# schematic.net
KiCad netlist of a schematic drawn in EasyEDA
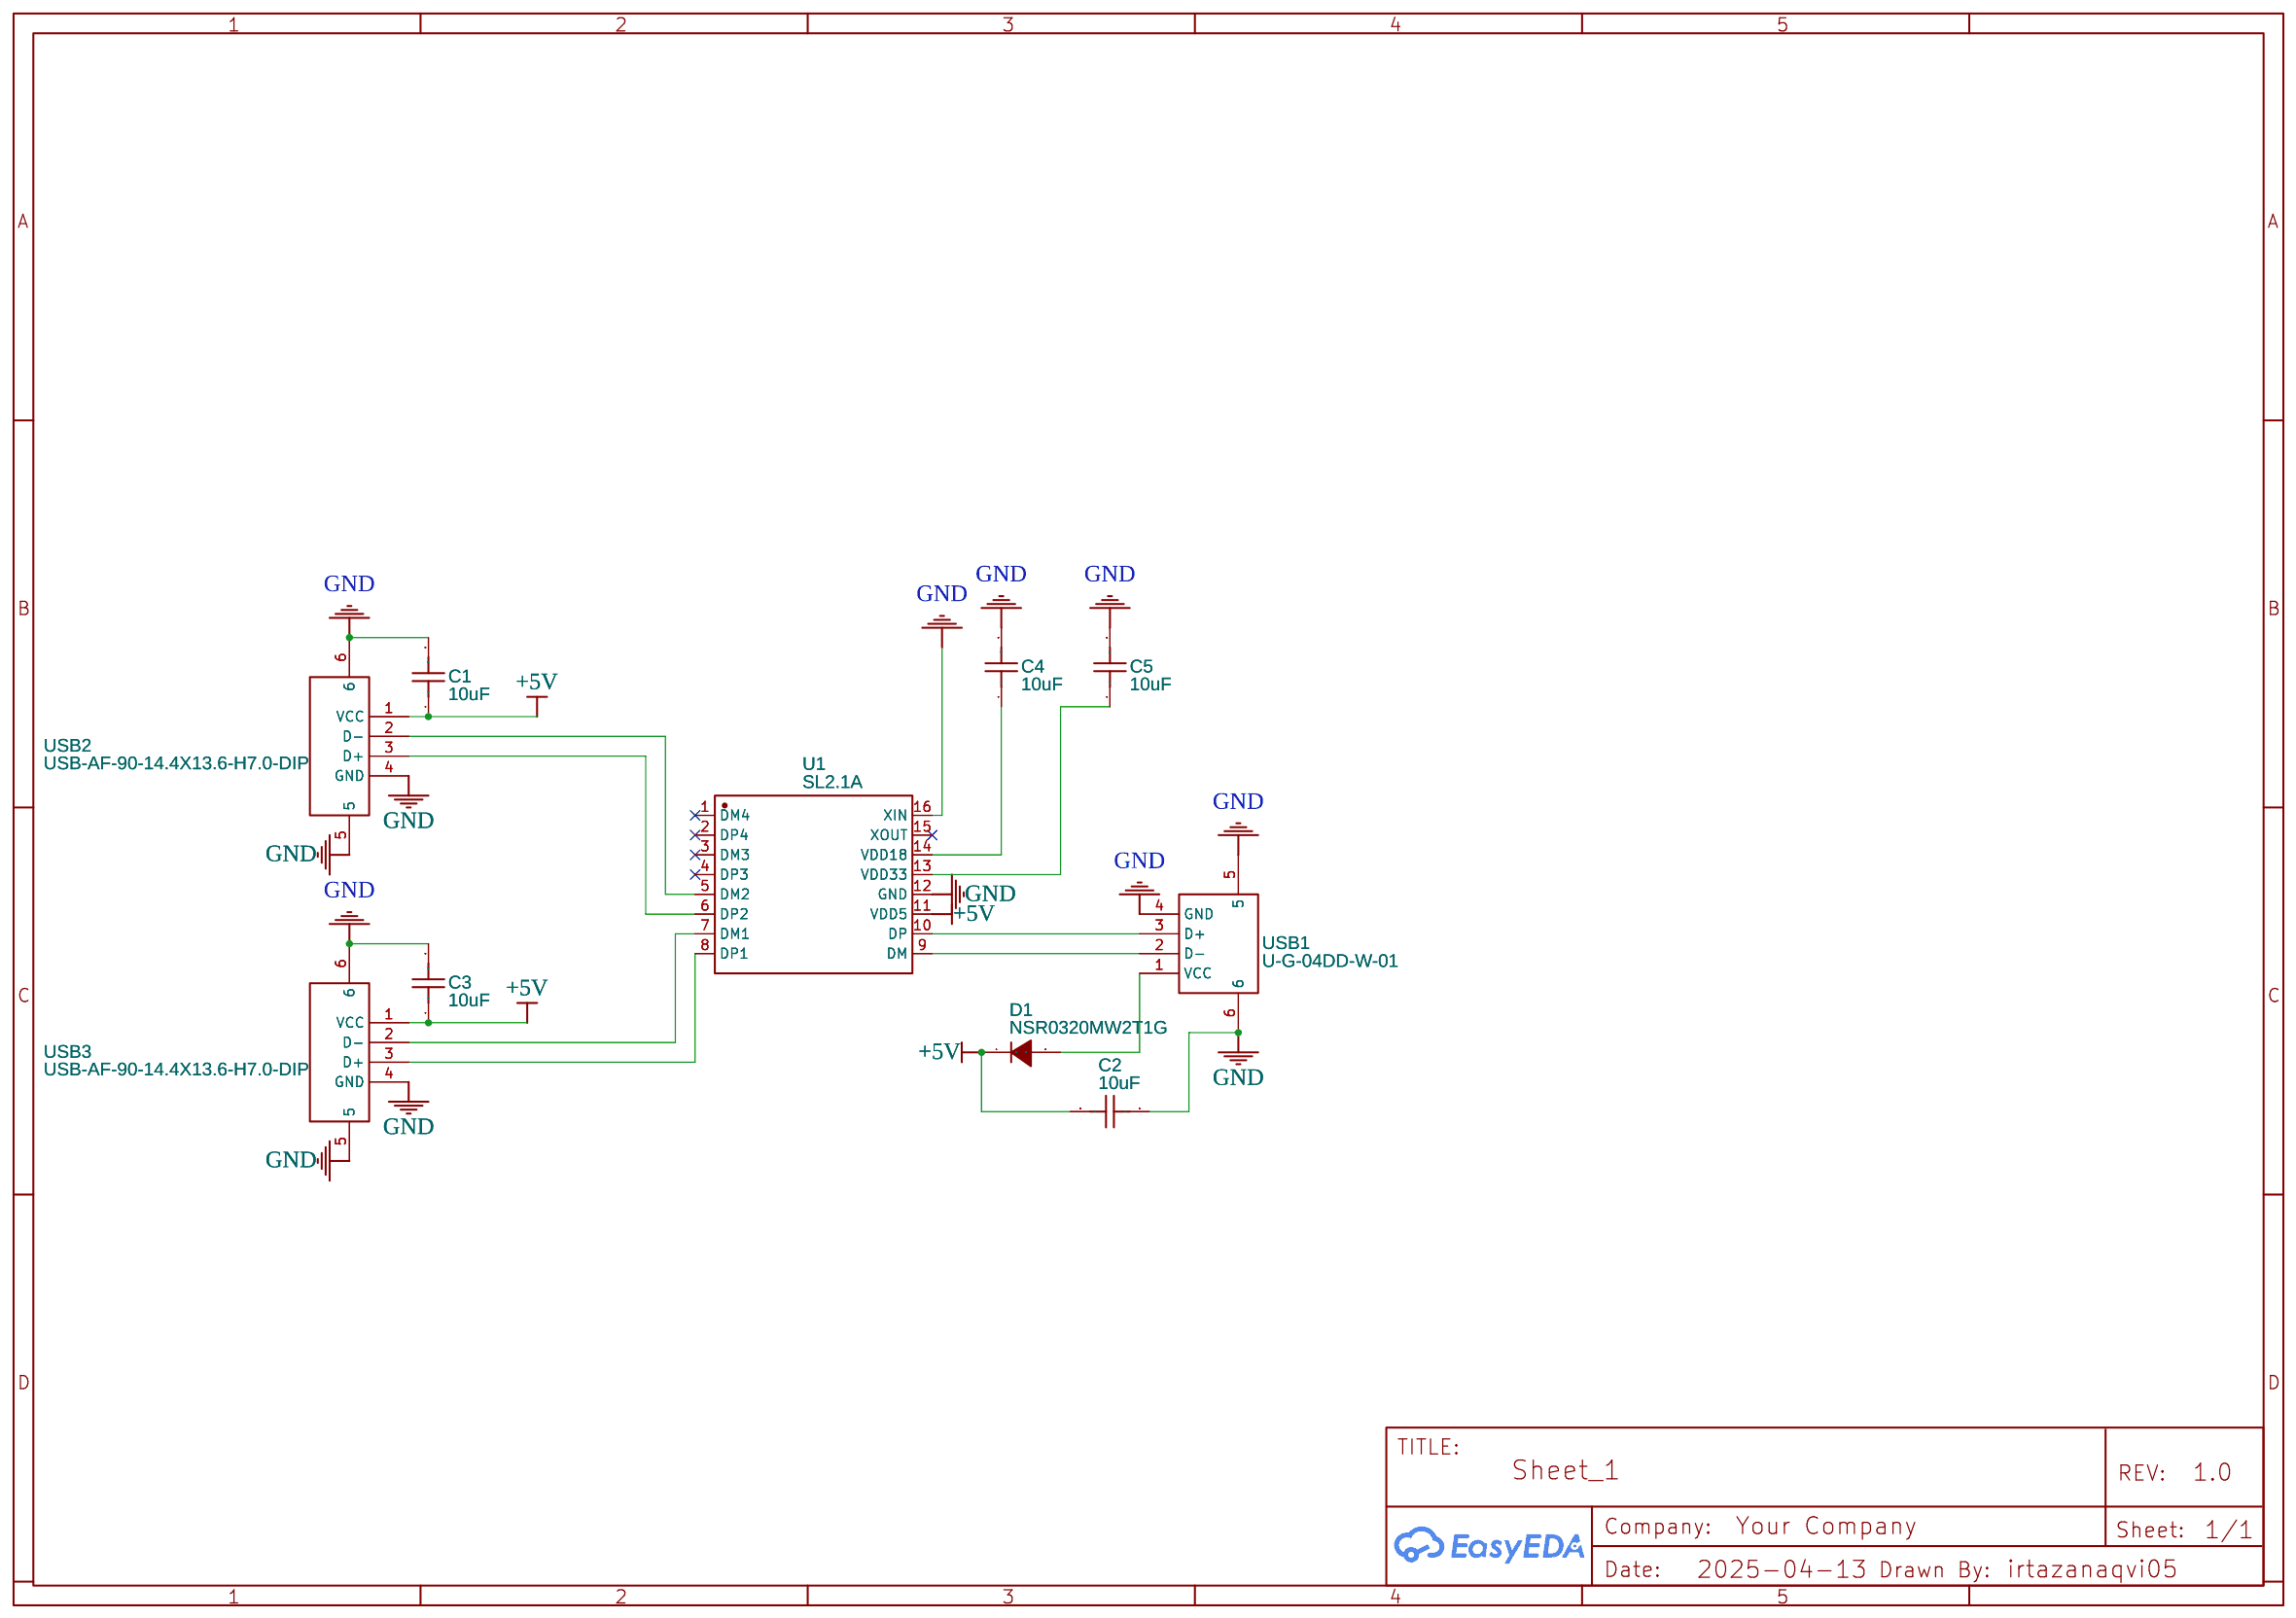
[diagram p0: schematic sheet]

(export (version "E")
  (design (tool "Eeschema 10.0.6"))
  (components
    (comp (ref "C1")
      (value "10uF")
      (fields
        (field (name "Manufacturer Part") "CL10A106KP8NNNC")
        (field (name "Manufacturer") "SAMSUNG(三星)")
      )
      (libsource (lib "") (part "CL10A106KP8NNNC"))
    )
    (comp (ref "C2")
      (value "10uF")
      (fields
        (field (name "Manufacturer Part") "CL10A106KP8NNNC")
        (field (name "Manufacturer") "SAMSUNG(三星)")
      )
      (libsource (lib "") (part "CL10A106KP8NNNC_1"))
    )
    (comp (ref "C3")
      (value "10uF")
      (fields
        (field (name "Manufacturer Part") "CL10A106KP8NNNC")
        (field (name "Manufacturer") "SAMSUNG(三星)")
      )
      (libsource (lib "") (part "CL10A106KP8NNNC"))
    )
    (comp (ref "C4")
      (value "10uF")
      (fields
        (field (name "Manufacturer Part") "CL10A106KP8NNNC")
        (field (name "Manufacturer") "SAMSUNG(三星)")
      )
      (libsource (lib "") (part "CL10A106KP8NNNC"))
    )
    (comp (ref "C5")
      (value "10uF")
      (fields
        (field (name "Manufacturer Part") "CL10A106KP8NNNC")
        (field (name "Manufacturer") "SAMSUNG(三星)")
      )
      (libsource (lib "") (part "CL10A106KP8NNNC"))
    )
    (comp (ref "D1")
      (value "NSR0320MW2T1G")
      (fields (field (name "Manufacturer") "onsemi(安森美)"))
      (libsource (lib "") (part "NSR0320MW2T1G"))
    )
    (comp (ref "U1")
      (value "SL2.1A")
      (fields (field (name "Manufacturer") "CoreChips(和芯润德)"))
      (libsource (lib "") (part "SL2.1A"))
    )
    (comp (ref "USB1")
      (value "U-G-04DD-W-01")
      (fields (field (name "Manufacturer Part") "U-G-O4DD-W-1") (field (name "Manufacturer") "韩国韩荣"))
      (libsource (lib "") (part "U-G-04DD-W-01"))
    )
    (comp (ref "USB2")
      (value "USB-AF-90-14.4X13.6-H7.0-DIP")
      (fields (field (name "Manufacturer Part") "903-131A1011D10100") (field (name "Manufacturer") "精拓金"))
      (libsource (lib "") (part "USB-AF-90-14.4X13.6-H7.0-DIP"))
    )
    (comp (ref "USB3")
      (value "USB-AF-90-14.4X13.6-H7.0-DIP")
      (fields (field (name "Manufacturer Part") "903-131A1011D10100") (field (name "Manufacturer") "精拓金"))
      (libsource (lib "") (part "USB-AF-90-14.4X13.6-H7.0-DIP"))
    )
  )
  (nets
    (net (code "1") (name "+5V") (class "Default")
      (node (ref "C1") (pin "1") (pinfunction "1_1") (pintype "unspecified"))
      (node (ref "C2") (pin "2") (pinfunction "2_2") (pintype "unspecified"))
      (node (ref "C3") (pin "1") (pinfunction "1_1") (pintype "unspecified"))
      (node (ref "D1") (pin "1") (pinfunction "C_1") (pintype "unspecified"))
      (node (ref "U1") (pin "11") (pinfunction "VDD5_11") (pintype "unspecified"))
      (node (ref "USB2") (pin "1") (pinfunction "VCC_1") (pintype "unspecified"))
      (node (ref "USB3") (pin "1") (pinfunction "VCC_1") (pintype "unspecified"))
    )
    (net (code "2") (name "GND") (class "Default")
      (node (ref "C1") (pin "2") (pinfunction "2_2") (pintype "unspecified"))
      (node (ref "C2") (pin "1") (pinfunction "1_1") (pintype "unspecified"))
      (node (ref "C3") (pin "2") (pinfunction "2_2") (pintype "unspecified"))
      (node (ref "C4") (pin "2") (pinfunction "2_2") (pintype "unspecified"))
      (node (ref "C5") (pin "2") (pinfunction "2_2") (pintype "unspecified"))
      (node (ref "U1") (pin "12") (pinfunction "GND_12") (pintype "unspecified"))
      (node (ref "U1") (pin "16") (pinfunction "XIN_16") (pintype "unspecified"))
      (node (ref "USB1") (pin "4") (pinfunction "GND_4") (pintype "unspecified"))
      (node (ref "USB1") (pin "5") (pinfunction "5_5") (pintype "unspecified"))
      (node (ref "USB1") (pin "6") (pinfunction "6_6") (pintype "unspecified"))
      (node (ref "USB2") (pin "4") (pinfunction "GND_4") (pintype "unspecified"))
      (node (ref "USB2") (pin "5") (pinfunction "5_5") (pintype "unspecified"))
      (node (ref "USB2") (pin "6") (pinfunction "6_6") (pintype "unspecified"))
      (node (ref "USB3") (pin "4") (pinfunction "GND_4") (pintype "unspecified"))
      (node (ref "USB3") (pin "5") (pinfunction "5_5") (pintype "unspecified"))
      (node (ref "USB3") (pin "6") (pinfunction "6_6") (pintype "unspecified"))
    )
    (net (code "3") (name "Net-(D1-A)") (class "Default")
      (node (ref "D1") (pin "2") (pinfunction "A_2") (pintype "unspecified"))
      (node (ref "USB1") (pin "1") (pinfunction "VCC_1") (pintype "unspecified"))
    )
    (net (code "4") (name "Net-(U1-DM)") (class "Default")
      (node (ref "U1") (pin "9") (pinfunction "DM_9") (pintype "unspecified"))
      (node (ref "USB1") (pin "2") (pinfunction "D-_2") (pintype "unspecified"))
    )
    (net (code "5") (name "Net-(U1-DM1)") (class "Default")
      (node (ref "U1") (pin "7") (pinfunction "DM1_7") (pintype "unspecified"))
      (node (ref "USB3") (pin "2") (pinfunction "D-_2") (pintype "unspecified"))
    )
    (net (code "6") (name "Net-(U1-DM2)") (class "Default")
      (node (ref "U1") (pin "5") (pinfunction "DM2_5") (pintype "unspecified"))
      (node (ref "USB2") (pin "2") (pinfunction "D-_2") (pintype "unspecified"))
    )
    (net (code "7") (name "Net-(U1-DP)") (class "Default")
      (node (ref "U1") (pin "10") (pinfunction "DP_10") (pintype "unspecified"))
      (node (ref "USB1") (pin "3") (pinfunction "D+_3") (pintype "unspecified"))
    )
    (net (code "8") (name "Net-(U1-DP1)") (class "Default")
      (node (ref "U1") (pin "8") (pinfunction "DP1_8") (pintype "unspecified"))
      (node (ref "USB3") (pin "3") (pinfunction "D+_3") (pintype "unspecified"))
    )
    (net (code "9") (name "Net-(U1-DP2)") (class "Default")
      (node (ref "U1") (pin "6") (pinfunction "DP2_6") (pintype "unspecified"))
      (node (ref "USB2") (pin "3") (pinfunction "D+_3") (pintype "unspecified"))
    )
    (net (code "10") (name "Net-(U1-VDD18)") (class "Default")
      (node (ref "C4") (pin "1") (pinfunction "1_1") (pintype "unspecified"))
      (node (ref "U1") (pin "14") (pinfunction "VDD18_14") (pintype "unspecified"))
    )
    (net (code "11") (name "Net-(U1-VDD33)") (class "Default")
      (node (ref "C5") (pin "1") (pinfunction "1_1") (pintype "unspecified"))
      (node (ref "U1") (pin "13") (pinfunction "VDD33_13") (pintype "unspecified"))
    )
    (net (code "12") (name "unconnected-(U1-DM3-Pad3)") (class "Default")
      (node (ref "U1") (pin "3") (pinfunction "DM3_3") (pintype "unspecified+no_connect"))
    )
    (net (code "13") (name "unconnected-(U1-DM4-Pad1)") (class "Default")
      (node (ref "U1") (pin "1") (pinfunction "DM4_1") (pintype "unspecified+no_connect"))
    )
    (net (code "14") (name "unconnected-(U1-DP3-Pad4)") (class "Default")
      (node (ref "U1") (pin "4") (pinfunction "DP3_4") (pintype "unspecified+no_connect"))
    )
    (net (code "15") (name "unconnected-(U1-DP4-Pad2)") (class "Default")
      (node (ref "U1") (pin "2") (pinfunction "DP4_2") (pintype "unspecified+no_connect"))
    )
    (net (code "16") (name "unconnected-(U1-XOUT-Pad15)") (class "Default")
      (node (ref "U1") (pin "15") (pinfunction "XOUT_15") (pintype "unspecified+no_connect"))
    )
  )
)
